# EEG_Signal_Input.net
KiCad netlist of a schematic drawn in Altium Designer
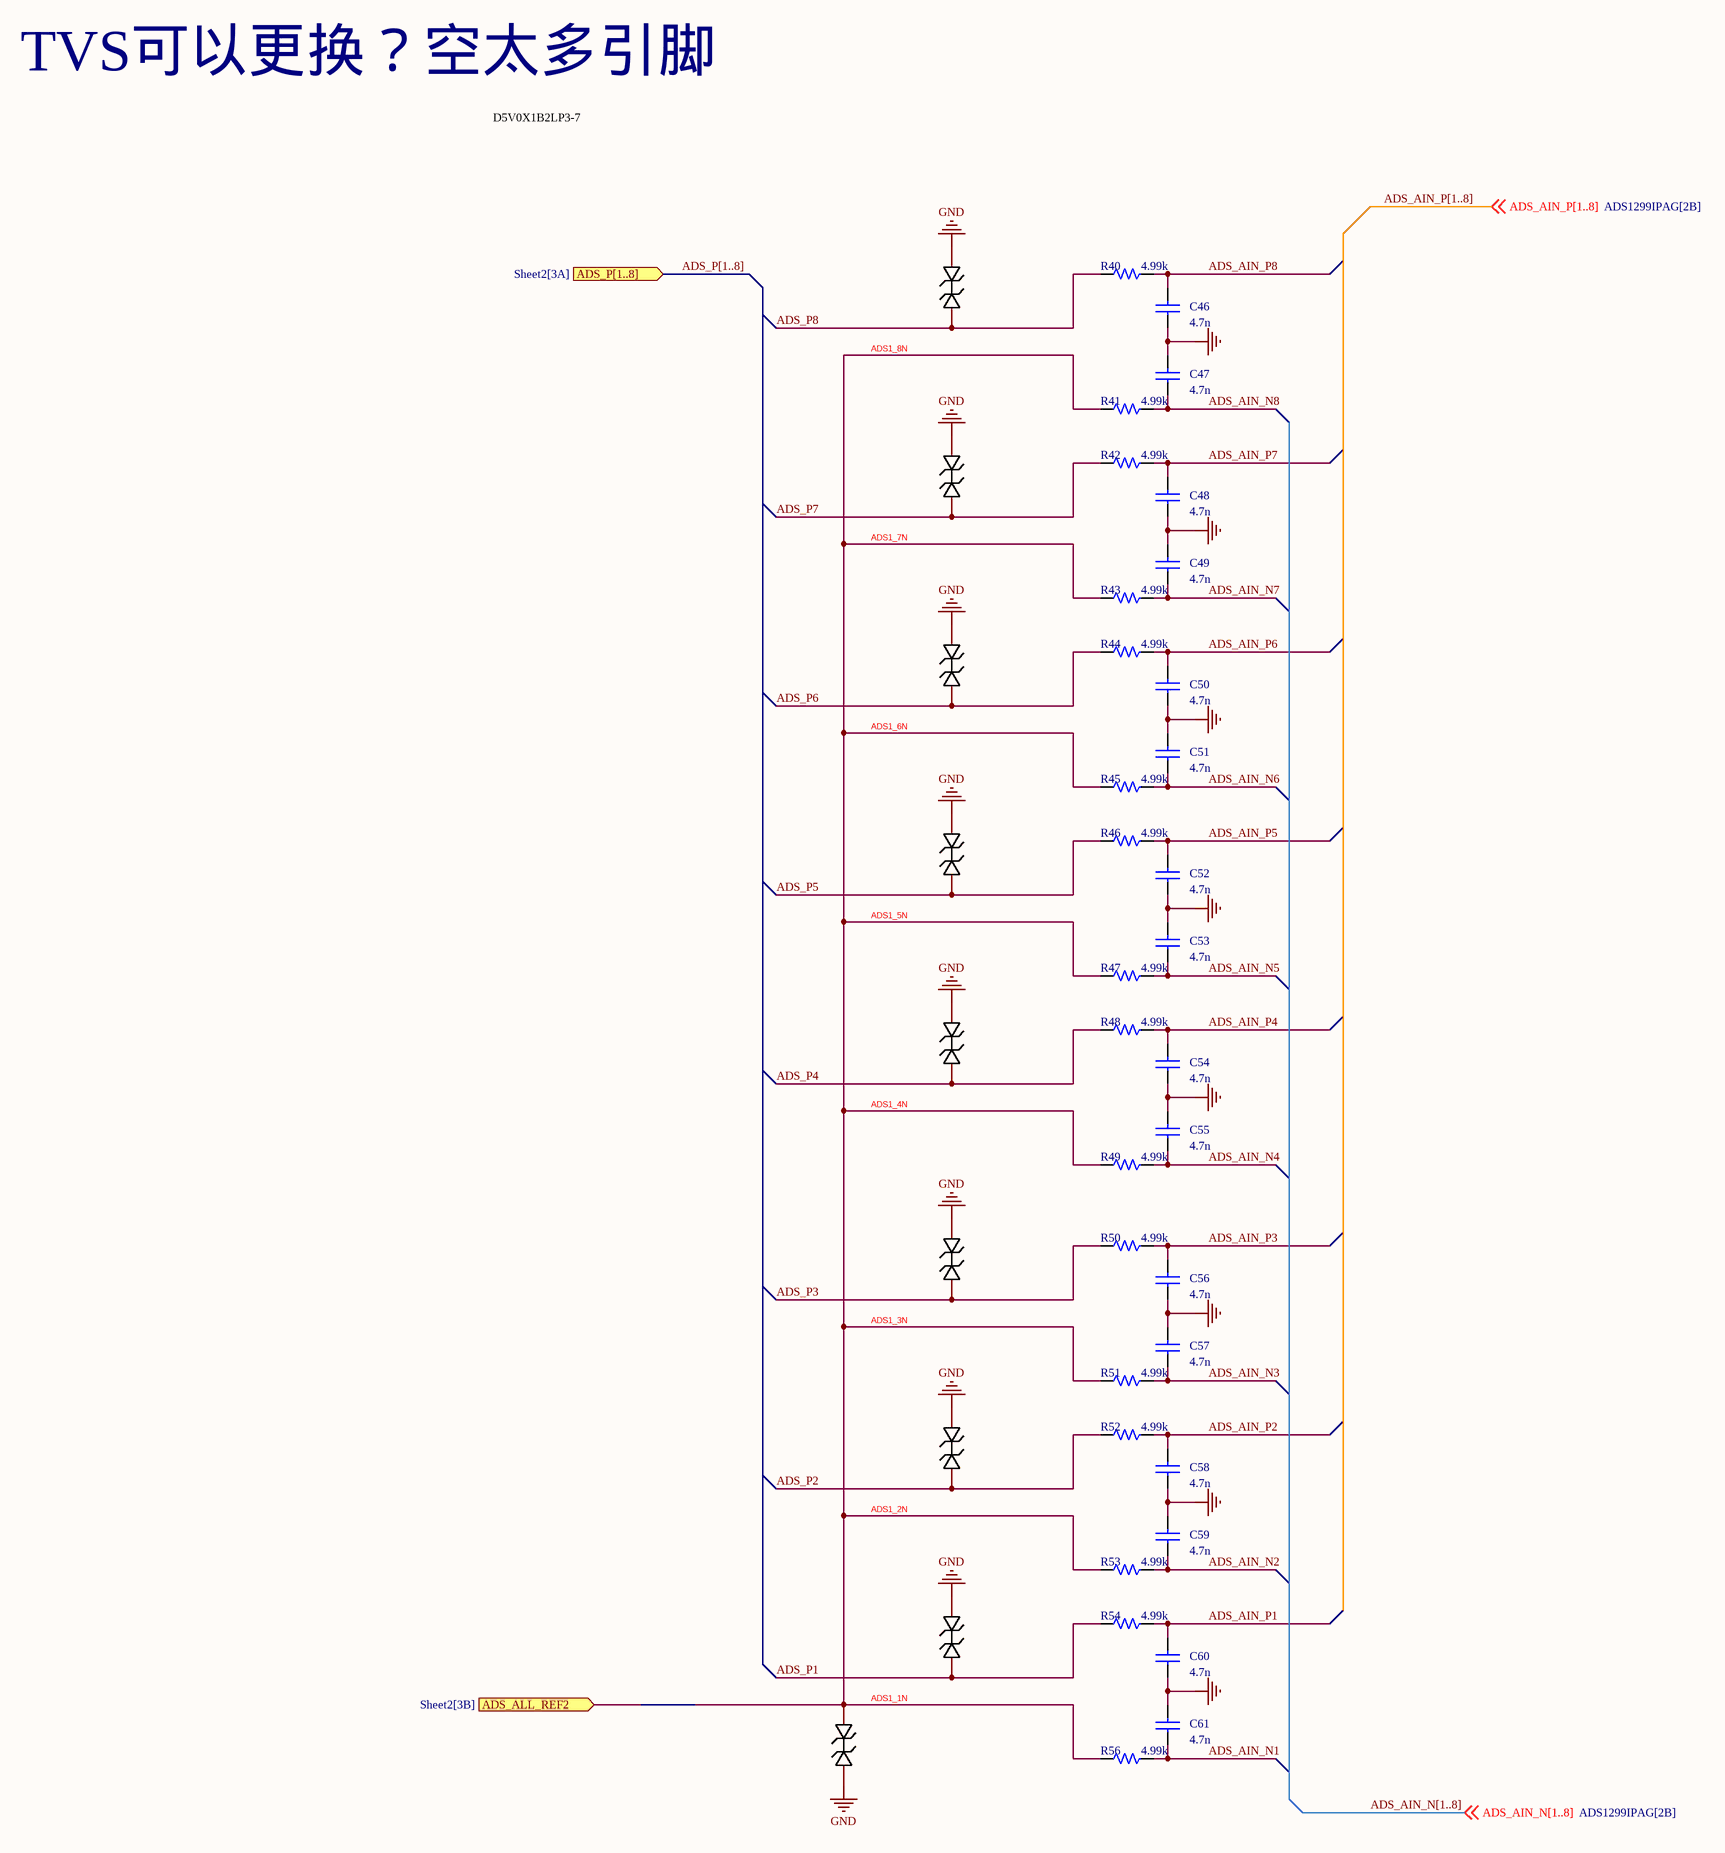
[diagram p0: EEG Signal Input.SchDoc]

(export (version "E")
  (design (tool "Eeschema 10.0.6"))
  (components
    (comp (ref "C46")
      (value "4.7n")
      (footprint "0201_C")
      (description "CAP CER 4700PF 50V X7R 0402")
      (fields
        (field (name "DISTRIBUTOR PART NUMBER") "C106208")
        (field (name "PART NUMBER") "CC0402KRX7R9BB472")
      )
      (libsource (lib "*") (part "CAP0402"))
    )
    (comp (ref "C47")
      (value "4.7n")
      (footprint "0201_C")
      (description "CAP CER 4700PF 50V X7R 0402")
      (fields
        (field (name "DISTRIBUTOR PART NUMBER") "C106208")
        (field (name "PART NUMBER") "CC0402KRX7R9BB472")
      )
      (libsource (lib "*") (part "CAP0402"))
    )
    (comp (ref "C48")
      (value "4.7n")
      (footprint "0201_C")
      (description "CAP CER 4700PF 50V X7R 0402")
      (fields
        (field (name "DISTRIBUTOR PART NUMBER") "C106208")
        (field (name "PART NUMBER") "CC0402KRX7R9BB472")
      )
      (libsource (lib "*") (part "CAP0402"))
    )
    (comp (ref "C49")
      (value "4.7n")
      (footprint "0201_C")
      (description "CAP CER 4700PF 50V X7R 0402")
      (fields
        (field (name "DISTRIBUTOR PART NUMBER") "C106208")
        (field (name "PART NUMBER") "CC0402KRX7R9BB472")
      )
      (libsource (lib "*") (part "CAP0402"))
    )
    (comp (ref "C50")
      (value "4.7n")
      (footprint "0201_C")
      (description "CAP CER 4700PF 50V X7R 0402")
      (fields
        (field (name "DISTRIBUTOR PART NUMBER") "C106208")
        (field (name "PART NUMBER") "CC0402KRX7R9BB472")
      )
      (libsource (lib "*") (part "CAP0402"))
    )
    (comp (ref "C51")
      (value "4.7n")
      (footprint "0201_C")
      (description "CAP CER 4700PF 50V X7R 0402")
      (fields
        (field (name "DISTRIBUTOR PART NUMBER") "C106208")
        (field (name "PART NUMBER") "CC0402KRX7R9BB472")
      )
      (libsource (lib "*") (part "CAP0402"))
    )
    (comp (ref "C52")
      (value "4.7n")
      (footprint "0201_C")
      (description "CAP CER 4700PF 50V X7R 0402")
      (fields
        (field (name "DISTRIBUTOR PART NUMBER") "C106208")
        (field (name "PART NUMBER") "CC0402KRX7R9BB472")
      )
      (libsource (lib "*") (part "CAP0402"))
    )
    (comp (ref "C53")
      (value "4.7n")
      (footprint "0201_C")
      (description "CAP CER 4700PF 50V X7R 0402")
      (fields
        (field (name "DISTRIBUTOR PART NUMBER") "C106208")
        (field (name "PART NUMBER") "CC0402KRX7R9BB472")
      )
      (libsource (lib "*") (part "CAP0402"))
    )
    (comp (ref "C54")
      (value "4.7n")
      (footprint "0201_C")
      (description "CAP CER 4700PF 50V X7R 0402")
      (fields
        (field (name "DISTRIBUTOR PART NUMBER") "C106208")
        (field (name "PART NUMBER") "CC0402KRX7R9BB472")
      )
      (libsource (lib "*") (part "CAP0402"))
    )
    (comp (ref "C55")
      (value "4.7n")
      (footprint "0201_C")
      (description "CAP CER 4700PF 50V X7R 0402")
      (fields
        (field (name "DISTRIBUTOR PART NUMBER") "C106208")
        (field (name "PART NUMBER") "CC0402KRX7R9BB472")
      )
      (libsource (lib "*") (part "CAP0402"))
    )
    (comp (ref "C56")
      (value "4.7n")
      (footprint "0201_C")
      (description "CAP CER 4700PF 50V X7R 0402")
      (fields
        (field (name "DISTRIBUTOR PART NUMBER") "C106208")
        (field (name "PART NUMBER") "CC0402KRX7R9BB472")
      )
      (libsource (lib "*") (part "CAP0402"))
    )
    (comp (ref "C57")
      (value "4.7n")
      (footprint "0201_C")
      (description "CAP CER 4700PF 50V X7R 0402")
      (fields
        (field (name "DISTRIBUTOR PART NUMBER") "C106208")
        (field (name "PART NUMBER") "CC0402KRX7R9BB472")
      )
      (libsource (lib "*") (part "CAP0402"))
    )
    (comp (ref "C58")
      (value "4.7n")
      (footprint "0201_C")
      (description "CAP CER 4700PF 50V X7R 0402")
      (fields
        (field (name "DISTRIBUTOR PART NUMBER") "C106208")
        (field (name "PART NUMBER") "CC0402KRX7R9BB472")
      )
      (libsource (lib "*") (part "CAP0402"))
    )
    (comp (ref "C59")
      (value "4.7n")
      (footprint "0201_C")
      (description "CAP CER 4700PF 50V X7R 0402")
      (fields
        (field (name "DISTRIBUTOR PART NUMBER") "C106208")
        (field (name "PART NUMBER") "CC0402KRX7R9BB472")
      )
      (libsource (lib "*") (part "CAP0402"))
    )
    (comp (ref "C60")
      (value "4.7n")
      (footprint "0201_C")
      (description "CAP CER 4700PF 50V X7R 0402")
      (fields
        (field (name "DISTRIBUTOR PART NUMBER") "C106208")
        (field (name "PART NUMBER") "CC0402KRX7R9BB472")
      )
      (libsource (lib "*") (part "CAP0402"))
    )
    (comp (ref "C61")
      (value "4.7n")
      (footprint "0201_C")
      (description "CAP CER 4700PF 50V X7R 0402")
      (fields
        (field (name "DISTRIBUTOR PART NUMBER") "C106208")
        (field (name "PART NUMBER") "CC0402KRX7R9BB472")
      )
      (libsource (lib "*") (part "CAP0402"))
    )
    (comp (ref "D4")
      (value "D5V0X1B2LP3-7")
      (footprint "X3-DFN0603-2_L0.6-W0.3-BI")
      (fields (field (name "MANUFACTURER") "DIODES(美台)"))
      (libsource (lib "altium-import") (part "root_1_D5V0X1B2LP3-7_"))
    )
    (comp (ref "D5")
      (value "D5V0X1B2LP3-7")
      (footprint "X3-DFN0603-2_L0.6-W0.3-BI")
      (fields (field (name "MANUFACTURER") "DIODES(美台)"))
      (libsource (lib "altium-import") (part "root_1_D5V0X1B2LP3-7_"))
    )
    (comp (ref "D6")
      (value "D5V0X1B2LP3-7")
      (footprint "X3-DFN0603-2_L0.6-W0.3-BI")
      (fields (field (name "MANUFACTURER") "DIODES(美台)"))
      (libsource (lib "altium-import") (part "root_1_D5V0X1B2LP3-7_"))
    )
    (comp (ref "D7")
      (value "D5V0X1B2LP3-7")
      (footprint "X3-DFN0603-2_L0.6-W0.3-BI")
      (fields (field (name "MANUFACTURER") "DIODES(美台)"))
      (libsource (lib "altium-import") (part "root_1_D5V0X1B2LP3-7_"))
    )
    (comp (ref "D8")
      (value "D5V0X1B2LP3-7")
      (footprint "X3-DFN0603-2_L0.6-W0.3-BI")
      (fields (field (name "MANUFACTURER") "DIODES(美台)"))
      (libsource (lib "altium-import") (part "root_1_D5V0X1B2LP3-7_"))
    )
    (comp (ref "D9")
      (value "D5V0X1B2LP3-7")
      (footprint "X3-DFN0603-2_L0.6-W0.3-BI")
      (fields (field (name "MANUFACTURER") "DIODES(美台)"))
      (libsource (lib "altium-import") (part "root_1_D5V0X1B2LP3-7_"))
    )
    (comp (ref "D10")
      (value "D5V0X1B2LP3-7")
      (footprint "X3-DFN0603-2_L0.6-W0.3-BI")
      (fields (field (name "MANUFACTURER") "DIODES(美台)"))
      (libsource (lib "altium-import") (part "root_1_D5V0X1B2LP3-7_"))
    )
    (comp (ref "D11")
      (value "D5V0X1B2LP3-7")
      (footprint "X3-DFN0603-2_L0.6-W0.3-BI")
      (fields (field (name "MANUFACTURER") "DIODES(美台)"))
      (libsource (lib "altium-import") (part "root_1_D5V0X1B2LP3-7_"))
    )
    (comp (ref "D12")
      (value "D5V0X1B2LP3-7")
      (footprint "X3-DFN0603-2_L0.6-W0.3-BI")
      (fields (field (name "MANUFACTURER") "DIODES(美台)"))
      (libsource (lib "altium-import") (part "root_3_D5V0X1B2LP3-7_"))
    )
    (comp (ref "R40")
      (value "4.99k")
      (footprint "0201_R")
      (description "RES SMD 4.99K OHM 1% 1/16W 0402")
      (fields
        (field (name "MANUFACTURER") "YAGEO")
        (field (name "MANUFACTURER PART NUMBER") "RC0402FR-074K99L")
      )
      (libsource (lib "*") (part "RES"))
    )
    (comp (ref "R41")
      (value "4.99k")
      (footprint "0201_R")
      (description "RES SMD 4.99K OHM 1% 1/16W 0402")
      (fields
        (field (name "MANUFACTURER") "YAGEO")
        (field (name "MANUFACTURER PART NUMBER") "RC0402FR-074K99L")
      )
      (libsource (lib "*") (part "RES"))
    )
    (comp (ref "R42")
      (value "4.99k")
      (footprint "0201_R")
      (description "RES SMD 4.99K OHM 1% 1/16W 0402")
      (fields
        (field (name "DISTRIBUTOR PART NUMBER") "C137965")
        (field (name "PART NUMBER") "RC0402FR-074K99L")
      )
      (libsource (lib "*") (part "RES"))
    )
    (comp (ref "R43")
      (value "4.99k")
      (footprint "0201_R")
      (description "RES SMD 4.99K OHM 1% 1/16W 0402")
      (fields
        (field (name "DISTRIBUTOR PART NUMBER") "C137965")
        (field (name "PART NUMBER") "RC0402FR-074K99L")
      )
      (libsource (lib "*") (part "RES"))
    )
    (comp (ref "R44")
      (value "4.99k")
      (footprint "0201_R")
      (description "RES SMD 4.99K OHM 1% 1/16W 0402")
      (fields
        (field (name "MANUFACTURER") "YAGEO")
        (field (name "MANUFACTURER PART NUMBER") "RC0402FR-074K99L")
      )
      (libsource (lib "*") (part "RES"))
    )
    (comp (ref "R45")
      (value "4.99k")
      (footprint "0201_R")
      (description "RES SMD 4.99K OHM 1% 1/16W 0402")
      (fields
        (field (name "MANUFACTURER") "YAGEO")
        (field (name "MANUFACTURER PART NUMBER") "RC0402FR-074K99L")
      )
      (libsource (lib "*") (part "RES"))
    )
    (comp (ref "R46")
      (value "4.99k")
      (footprint "0201_R")
      (description "RES SMD 4.99K OHM 1% 1/16W 0402")
      (fields
        (field (name "DISTRIBUTOR PART NUMBER") "C137965")
        (field (name "PART NUMBER") "RC0402FR-074K99L")
      )
      (libsource (lib "*") (part "RES"))
    )
    (comp (ref "R47")
      (value "4.99k")
      (footprint "0201_R")
      (description "RES SMD 4.99K OHM 1% 1/16W 0402")
      (fields
        (field (name "DISTRIBUTOR PART NUMBER") "C137965")
        (field (name "PART NUMBER") "RC0402FR-074K99L")
      )
      (libsource (lib "*") (part "RES"))
    )
    (comp (ref "R48")
      (value "4.99k")
      (footprint "0201_R")
      (description "RES SMD 4.99K OHM 1% 1/16W 0402")
      (fields
        (field (name "DISTRIBUTOR PART NUMBER") "C137965")
        (field (name "PART NUMBER") "RC0402FR-074K99L")
      )
      (libsource (lib "*") (part "RES"))
    )
    (comp (ref "R49")
      (value "4.99k")
      (footprint "0201_R")
      (description "RES SMD 4.99K OHM 1% 1/16W 0402")
      (fields
        (field (name "DISTRIBUTOR PART NUMBER") "C137965")
        (field (name "PART NUMBER") "RC0402FR-074K99L")
      )
      (libsource (lib "*") (part "RES"))
    )
    (comp (ref "R50")
      (value "4.99k")
      (footprint "0201_R")
      (description "RES SMD 4.99K OHM 1% 1/16W 0402")
      (fields
        (field (name "DISTRIBUTOR PART NUMBER") "C137965")
        (field (name "PART NUMBER") "RC0402FR-074K99L")
      )
      (libsource (lib "*") (part "RES"))
    )
    (comp (ref "R51")
      (value "4.99k")
      (footprint "0201_R")
      (description "RES SMD 4.99K OHM 1% 1/16W 0402")
      (fields
        (field (name "DISTRIBUTOR PART NUMBER") "C137965")
        (field (name "PART NUMBER") "RC0402FR-074K99L")
      )
      (libsource (lib "*") (part "RES"))
    )
    (comp (ref "R52")
      (value "4.99k")
      (footprint "0201_R")
      (description "RES SMD 4.99K OHM 1% 1/16W 0402")
      (fields
        (field (name "MANUFACTURER") "YAGEO")
        (field (name "MANUFACTURER PART NUMBER") "RC0402FR-074K99L")
      )
      (libsource (lib "*") (part "RES"))
    )
    (comp (ref "R53")
      (value "4.99k")
      (footprint "0201_R")
      (description "RES SMD 4.99K OHM 1% 1/16W 0402")
      (fields
        (field (name "MANUFACTURER") "YAGEO")
        (field (name "MANUFACTURER PART NUMBER") "RC0402FR-074K99L")
      )
      (libsource (lib "*") (part "RES"))
    )
    (comp (ref "R54")
      (value "4.99k")
      (footprint "0201_R")
      (description "RES SMD 4.99K OHM 1% 1/16W 0402")
      (fields
        (field (name "DISTRIBUTOR PART NUMBER") "C137965")
        (field (name "PART NUMBER") "RC0402FR-074K99L")
      )
      (libsource (lib "*") (part "RES"))
    )
    (comp (ref "R56")
      (value "4.99k")
      (footprint "0201_R")
      (description "RES SMD 4.99K OHM 1% 1/16W 0402")
      (fields
        (field (name "DISTRIBUTOR PART NUMBER") "C137965")
        (field (name "PART NUMBER") "RC0402FR-074K99L")
      )
      (libsource (lib "*") (part "RES"))
    )
  )
  (nets
    (net (code "1") (name "/ADS1_1N") (class "Default")
      (node (ref "D12") (pin "1") (pinfunction "1_1") (pintype "passive"))
      (node (ref "R41") (pin "2") (pinfunction "2_2") (pintype "passive"))
      (node (ref "R43") (pin "2") (pinfunction "2_2") (pintype "passive"))
      (node (ref "R45") (pin "2") (pinfunction "2_2") (pintype "passive"))
      (node (ref "R47") (pin "2") (pinfunction "2_2") (pintype "passive"))
      (node (ref "R49") (pin "2") (pinfunction "2_2") (pintype "passive"))
      (node (ref "R51") (pin "2") (pinfunction "2_2") (pintype "passive"))
      (node (ref "R53") (pin "2") (pinfunction "2_2") (pintype "passive"))
      (node (ref "R56") (pin "2") (pinfunction "2_2") (pintype "passive"))
    )
    (net (code "2") (name "/ADS_P1") (class "Default")
      (node (ref "D11") (pin "1") (pinfunction "1_1") (pintype "passive"))
      (node (ref "R54") (pin "2") (pinfunction "2_2") (pintype "passive"))
    )
    (net (code "3") (name "/ADS_P2") (class "Default")
      (node (ref "D10") (pin "1") (pinfunction "1_1") (pintype "passive"))
      (node (ref "R52") (pin "2") (pinfunction "2_2") (pintype "passive"))
    )
    (net (code "4") (name "/ADS_P3") (class "Default")
      (node (ref "D9") (pin "1") (pinfunction "1_1") (pintype "passive"))
      (node (ref "R50") (pin "2") (pinfunction "2_2") (pintype "passive"))
    )
    (net (code "5") (name "/ADS_P4") (class "Default")
      (node (ref "D8") (pin "1") (pinfunction "1_1") (pintype "passive"))
      (node (ref "R48") (pin "2") (pinfunction "2_2") (pintype "passive"))
    )
    (net (code "6") (name "/ADS_P5") (class "Default")
      (node (ref "D7") (pin "1") (pinfunction "1_1") (pintype "passive"))
      (node (ref "R46") (pin "2") (pinfunction "2_2") (pintype "passive"))
    )
    (net (code "7") (name "/ADS_P6") (class "Default")
      (node (ref "D6") (pin "1") (pinfunction "1_1") (pintype "passive"))
      (node (ref "R44") (pin "2") (pinfunction "2_2") (pintype "passive"))
    )
    (net (code "8") (name "/ADS_P7") (class "Default")
      (node (ref "D5") (pin "1") (pinfunction "1_1") (pintype "passive"))
      (node (ref "R42") (pin "2") (pinfunction "2_2") (pintype "passive"))
    )
    (net (code "9") (name "/ADS_P8") (class "Default")
      (node (ref "D4") (pin "1") (pinfunction "1_1") (pintype "passive"))
      (node (ref "R40") (pin "2") (pinfunction "2_2") (pintype "passive"))
    )
    (net (code "11") (name "ADS_AIN_N1") (class "Default")
      (node (ref "C61") (pin "1") (pinfunction "1_1") (pintype "passive"))
      (node (ref "R56") (pin "1") (pinfunction "1_1") (pintype "passive"))
    )
    (net (code "12") (name "ADS_AIN_N2") (class "Default")
      (node (ref "C59") (pin "1") (pinfunction "1_1") (pintype "passive"))
      (node (ref "R53") (pin "1") (pinfunction "1_1") (pintype "passive"))
    )
    (net (code "13") (name "ADS_AIN_N3") (class "Default")
      (node (ref "C57") (pin "1") (pinfunction "1_1") (pintype "passive"))
      (node (ref "R51") (pin "1") (pinfunction "1_1") (pintype "passive"))
    )
    (net (code "14") (name "ADS_AIN_N4") (class "Default")
      (node (ref "C55") (pin "1") (pinfunction "1_1") (pintype "passive"))
      (node (ref "R49") (pin "1") (pinfunction "1_1") (pintype "passive"))
    )
    (net (code "15") (name "ADS_AIN_N5") (class "Default")
      (node (ref "C53") (pin "1") (pinfunction "1_1") (pintype "passive"))
      (node (ref "R47") (pin "1") (pinfunction "1_1") (pintype "passive"))
    )
    (net (code "16") (name "ADS_AIN_N6") (class "Default")
      (node (ref "C51") (pin "1") (pinfunction "1_1") (pintype "passive"))
      (node (ref "R45") (pin "1") (pinfunction "1_1") (pintype "passive"))
    )
    (net (code "17") (name "ADS_AIN_N7") (class "Default")
      (node (ref "C49") (pin "1") (pinfunction "1_1") (pintype "passive"))
      (node (ref "R43") (pin "1") (pinfunction "1_1") (pintype "passive"))
    )
    (net (code "18") (name "ADS_AIN_N8") (class "Default")
      (node (ref "C47") (pin "1") (pinfunction "1_1") (pintype "passive"))
      (node (ref "R41") (pin "1") (pinfunction "1_1") (pintype "passive"))
    )
    (net (code "20") (name "ADS_AIN_P1") (class "Default")
      (node (ref "C60") (pin "2") (pinfunction "2_2") (pintype "passive"))
      (node (ref "R54") (pin "1") (pinfunction "1_1") (pintype "passive"))
    )
    (net (code "21") (name "ADS_AIN_P2") (class "Default")
      (node (ref "C58") (pin "2") (pinfunction "2_2") (pintype "passive"))
      (node (ref "R52") (pin "1") (pinfunction "1_1") (pintype "passive"))
    )
    (net (code "22") (name "ADS_AIN_P3") (class "Default")
      (node (ref "C56") (pin "2") (pinfunction "2_2") (pintype "passive"))
      (node (ref "R50") (pin "1") (pinfunction "1_1") (pintype "passive"))
    )
    (net (code "23") (name "ADS_AIN_P4") (class "Default")
      (node (ref "C54") (pin "2") (pinfunction "2_2") (pintype "passive"))
      (node (ref "R48") (pin "1") (pinfunction "1_1") (pintype "passive"))
    )
    (net (code "24") (name "ADS_AIN_P5") (class "Default")
      (node (ref "C52") (pin "2") (pinfunction "2_2") (pintype "passive"))
      (node (ref "R46") (pin "1") (pinfunction "1_1") (pintype "passive"))
    )
    (net (code "25") (name "ADS_AIN_P6") (class "Default")
      (node (ref "C50") (pin "2") (pinfunction "2_2") (pintype "passive"))
      (node (ref "R44") (pin "1") (pinfunction "1_1") (pintype "passive"))
    )
    (net (code "26") (name "ADS_AIN_P7") (class "Default")
      (node (ref "C48") (pin "2") (pinfunction "2_2") (pintype "passive"))
      (node (ref "R42") (pin "1") (pinfunction "1_1") (pintype "passive"))
    )
    (net (code "27") (name "ADS_AIN_P8") (class "Default")
      (node (ref "C46") (pin "2") (pinfunction "2_2") (pintype "passive"))
      (node (ref "R40") (pin "1") (pinfunction "1_1") (pintype "passive"))
    )
    (net (code "29") (name "GND") (class "Default")
      (node (ref "C46") (pin "1") (pinfunction "1_1") (pintype "passive"))
      (node (ref "C47") (pin "2") (pinfunction "2_2") (pintype "passive"))
      (node (ref "C48") (pin "1") (pinfunction "1_1") (pintype "passive"))
      (node (ref "C49") (pin "2") (pinfunction "2_2") (pintype "passive"))
      (node (ref "C50") (pin "1") (pinfunction "1_1") (pintype "passive"))
      (node (ref "C51") (pin "2") (pinfunction "2_2") (pintype "passive"))
      (node (ref "C52") (pin "1") (pinfunction "1_1") (pintype "passive"))
      (node (ref "C53") (pin "2") (pinfunction "2_2") (pintype "passive"))
      (node (ref "C54") (pin "1") (pinfunction "1_1") (pintype "passive"))
      (node (ref "C55") (pin "2") (pinfunction "2_2") (pintype "passive"))
      (node (ref "C56") (pin "1") (pinfunction "1_1") (pintype "passive"))
      (node (ref "C57") (pin "2") (pinfunction "2_2") (pintype "passive"))
      (node (ref "C58") (pin "1") (pinfunction "1_1") (pintype "passive"))
      (node (ref "C59") (pin "2") (pinfunction "2_2") (pintype "passive"))
      (node (ref "C60") (pin "1") (pinfunction "1_1") (pintype "passive"))
      (node (ref "C61") (pin "2") (pinfunction "2_2") (pintype "passive"))
      (node (ref "D10") (pin "2") (pinfunction "2_2") (pintype "passive"))
      (node (ref "D11") (pin "2") (pinfunction "2_2") (pintype "passive"))
      (node (ref "D12") (pin "2") (pinfunction "2_2") (pintype "passive"))
      (node (ref "D4") (pin "2") (pinfunction "2_2") (pintype "passive"))
      (node (ref "D5") (pin "2") (pinfunction "2_2") (pintype "passive"))
      (node (ref "D6") (pin "2") (pinfunction "2_2") (pintype "passive"))
      (node (ref "D7") (pin "2") (pinfunction "2_2") (pintype "passive"))
      (node (ref "D8") (pin "2") (pinfunction "2_2") (pintype "passive"))
      (node (ref "D9") (pin "2") (pinfunction "2_2") (pintype "passive"))
    )
  )
)
